# max31855-breakout.net
KiCad netlist of a schematic drawn in EAGLE
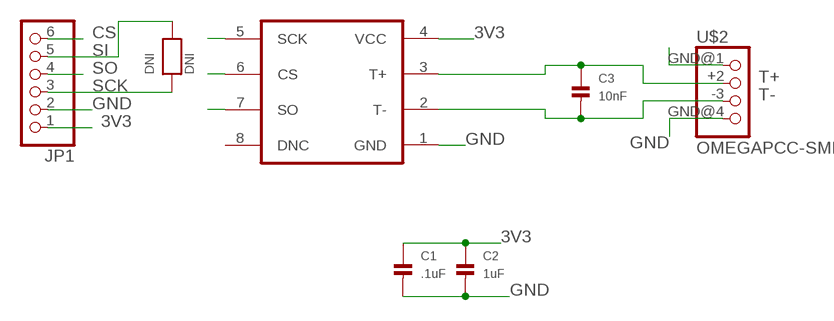
[diagram p0: schematic, sheet 1]

(export (version "E")
  (design (tool "Eeschema 10.0.6"))
  (components
    (comp (ref "C1")
      (value ".1uF")
      (footprint "eagle-import:0603")
      (libsource (lib "eagle-import") (part "CAP_CERAMIC0603"))
    )
    (comp (ref "C2")
      (value "1uF")
      (footprint "eagle-import:0603")
      (libsource (lib "eagle-import") (part "CAP_CERAMIC0603"))
    )
    (comp (ref "C3")
      (value "10nF")
      (footprint "eagle-import:0603")
      (libsource (lib "eagle-import") (part "CAP_CERAMIC0603"))
    )
    (comp (ref "DNI")
      (value "DNI")
      (footprint "eagle-import:0603")
      (libsource (lib "eagle-import") (part "RESISTOR0603"))
    )
    (comp (ref "JP1")
      (value "HEADER-1X6ROUND")
      (footprint "eagle-import:1X06_ROUND")
      (libsource (lib "eagle-import") (part "HEADER-1X6ROUND"))
    )
    (comp (ref "U$1")
      (value "MAX31855")
      (footprint "eagle-import:SO-08")
      (libsource (lib "eagle-import") (part "MAX31855"))
    )
    (comp (ref "U$2")
      (value "OMEGAPCC-SMP")
      (footprint "eagle-import:PCC-SMP")
      (libsource (lib "eagle-import") (part "OMEGAPCC-SMP"))
    )
  )
  (nets
    (net (code "1") (name "/3V3") (class "Default")
      (node (ref "C1") (pin "1") (pinfunction "P$1_1") (pintype "passive"))
      (node (ref "C2") (pin "1") (pinfunction "P$1_1") (pintype "passive"))
      (node (ref "JP1") (pin "1") (pinfunction "1_1") (pintype "passive"))
      (node (ref "U$1") (pin "4") (pinfunction "VCC_4") (pintype "bidirectional"))
    )
    (net (code "2") (name "/CS") (class "Default")
      (node (ref "JP1") (pin "6") (pinfunction "6_6") (pintype "passive"))
      (node (ref "U$1") (pin "6") (pinfunction "CS_6") (pintype "bidirectional"))
    )
    (net (code "3") (name "/GND") (class "Default")
      (node (ref "C1") (pin "2") (pinfunction "P$2_2") (pintype "passive"))
      (node (ref "C2") (pin "2") (pinfunction "P$2_2") (pintype "passive"))
      (node (ref "JP1") (pin "2") (pinfunction "2_2") (pintype "passive"))
      (node (ref "U$1") (pin "1") (pinfunction "GND_1") (pintype "bidirectional"))
      (node (ref "U$2") (pin "GND@1") (pinfunction "1_GND@1") (pintype "passive"))
      (node (ref "U$2") (pin "GND@4") (pinfunction "4_GND@4") (pintype "passive"))
    )
    (net (code "4") (name "/SCK") (class "Default")
      (node (ref "DNI") (pin "1") (pinfunction "1_1") (pintype "passive"))
      (node (ref "JP1") (pin "3") (pinfunction "3_3") (pintype "passive"))
      (node (ref "U$1") (pin "5") (pinfunction "SCK_5") (pintype "bidirectional"))
    )
    (net (code "5") (name "/SI") (class "Default")
      (node (ref "DNI") (pin "2") (pinfunction "2_2") (pintype "passive"))
      (node (ref "JP1") (pin "5") (pinfunction "5_5") (pintype "passive"))
    )
    (net (code "6") (name "/SO") (class "Default")
      (node (ref "JP1") (pin "4") (pinfunction "4_4") (pintype "passive"))
      (node (ref "U$1") (pin "7") (pinfunction "SO_7") (pintype "bidirectional"))
    )
    (net (code "7") (name "/T+") (class "Default")
      (node (ref "C3") (pin "1") (pinfunction "P$1_1") (pintype "passive"))
      (node (ref "U$1") (pin "3") (pinfunction "T+_3") (pintype "bidirectional"))
      (node (ref "U$2") (pin "+2") (pinfunction "2_+2") (pintype "passive"))
    )
    (net (code "8") (name "/T-") (class "Default")
      (node (ref "C3") (pin "2") (pinfunction "P$2_2") (pintype "passive"))
      (node (ref "U$1") (pin "2") (pinfunction "T-_2") (pintype "bidirectional"))
      (node (ref "U$2") (pin "-3") (pinfunction "3_-3") (pintype "passive"))
    )
    (net (code "9") (name "unconnected-(U$1-DNC-Pad8)") (class "Default")
      (node (ref "U$1") (pin "8") (pinfunction "DNC_8") (pintype "bidirectional"))
    )
  )
)
